# LCD.net
KiCad netlist of a schematic drawn in Altium Designer
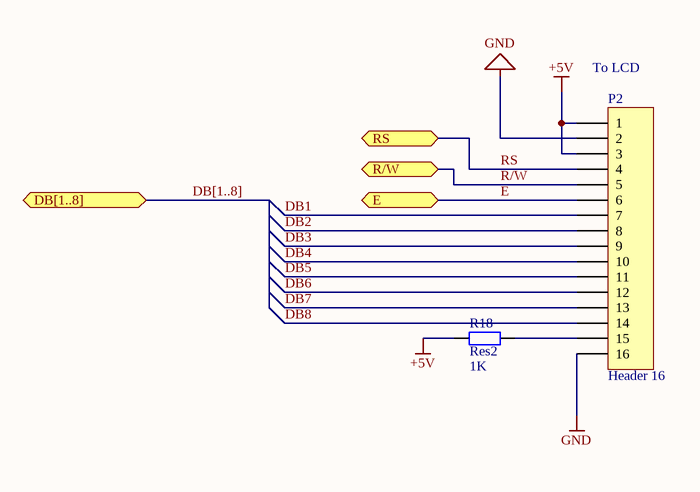
[diagram p0: LCD.SchDoc]

(export (version "E")
  (design (tool "Eeschema 10.0.6"))
  (components
    (comp (ref "P2")
      (value "Header 16")
      (footprint "S16B-PUDSS-1")
      (description "Header, 16-Pin")
      (fields (field (name "PUBLISHER") "Altium Limited"))
      (libsource (lib "Miscellaneous Connectors") (part "Header 16"))
    )
    (comp (ref "R18")
      (value "Res2")
      (footprint "0603")
      (description "Resistor")
      (fields (field (name "ALTIUM_VALUE") "1K") (field (name "PUBLISHER") "Altium Limited"))
      (libsource (lib "Miscellaneous Devices") (part "Res2"))
    )
  )
  (nets
    (net (code "1") (name "+5V") (class "Default")
      (node (ref "P2") (pin "1") (pinfunction "1_1") (pintype "passive"))
      (node (ref "P2") (pin "3") (pinfunction "3_3") (pintype "passive"))
      (node (ref "R18") (pin "1") (pinfunction "1_1") (pintype "passive"))
    )
    (net (code "2") (name "/DB1") (class "Default")
      (node (ref "P2") (pin "7") (pinfunction "7_7") (pintype "passive"))
    )
    (net (code "3") (name "/DB2") (class "Default")
      (node (ref "P2") (pin "8") (pinfunction "8_8") (pintype "passive"))
    )
    (net (code "4") (name "/DB3") (class "Default")
      (node (ref "P2") (pin "9") (pinfunction "9_9") (pintype "passive"))
    )
    (net (code "5") (name "/DB4") (class "Default")
      (node (ref "P2") (pin "10") (pinfunction "10_10") (pintype "passive"))
    )
    (net (code "6") (name "/DB5") (class "Default")
      (node (ref "P2") (pin "11") (pinfunction "11_11") (pintype "passive"))
    )
    (net (code "7") (name "/DB6") (class "Default")
      (node (ref "P2") (pin "12") (pinfunction "12_12") (pintype "passive"))
    )
    (net (code "8") (name "/DB7") (class "Default")
      (node (ref "P2") (pin "13") (pinfunction "13_13") (pintype "passive"))
    )
    (net (code "9") (name "/DB8") (class "Default")
      (node (ref "P2") (pin "14") (pinfunction "14_14") (pintype "passive"))
    )
    (net (code "11") (name "/E") (class "Default")
      (node (ref "P2") (pin "6") (pinfunction "6_6") (pintype "passive"))
    )
    (net (code "12") (name "/RS") (class "Default")
      (node (ref "P2") (pin "4") (pinfunction "4_4") (pintype "passive"))
    )
    (net (code "13") (name "/R{slash}W") (class "Default")
      (node (ref "P2") (pin "5") (pinfunction "5_5") (pintype "passive"))
    )
    (net (code "14") (name "GND") (class "Default")
      (node (ref "P2") (pin "16") (pinfunction "16_16") (pintype "passive"))
      (node (ref "P2") (pin "2") (pinfunction "2_2") (pintype "passive"))
    )
    (net (code "15") (name "Net-(P2-Pad15)") (class "Default")
      (node (ref "P2") (pin "15") (pinfunction "15_15") (pintype "passive"))
      (node (ref "R18") (pin "2") (pinfunction "2_2") (pintype "passive"))
    )
  )
)
